# Ethernet.net
KiCad netlist of a schematic drawn in Altium Designer
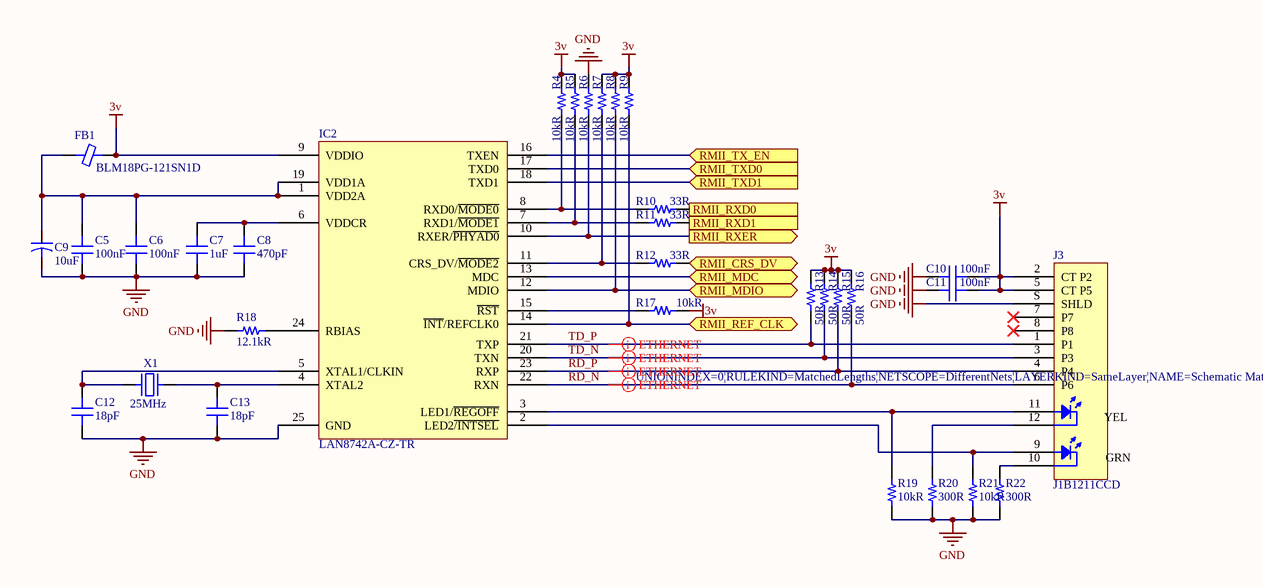
[diagram p0: Ethernet.SchDoc]

(export (version "E")
  (design (tool "Eeschema 10.0.6"))
  (components
    (comp (ref "C5")
      (value "100nF")
      (footprint "CAP 0603/1608")
      (description "Ceramic, SMT Capacitor")
      (fields
        (field (name "MANUFACTURER") "KEMET")
        (field (name "MANUFACTURER PART NUMBER") "C0603C104Z3VACTU")
      )
      (libsource (lib "yildizIoT Library") (part "Capacitor - Ceramic"))
    )
    (comp (ref "C6")
      (value "100nF")
      (footprint "CAP 0603/1608")
      (description "Ceramic, SMT Capacitor")
      (fields
        (field (name "MANUFACTURER") "KEMET")
        (field (name "MANUFACTURER PART NUMBER") "C0603C104Z3VACTU")
      )
      (libsource (lib "yildizIoT Library") (part "Capacitor - Ceramic"))
    )
    (comp (ref "C7")
      (value "1uF")
      (footprint "CAP 0603/1608")
      (description "Ceramic, SMT Capacitor")
      (fields
        (field (name "MANUFACTURER") "Samsung")
        (field (name "MANUFACTURER PART NUMBER") "CL10A105KP8NNNC")
      )
      (libsource (lib "yildizIoT Library") (part "Capacitor - Ceramic"))
    )
    (comp (ref "C8")
      (value "470pF")
      (footprint "CAP 0603/1608")
      (description "Ceramic, SMT Capacitor")
      (fields
        (field (name "MANUFACTURER") "Yageo")
        (field (name "MANUFACTURER PART NUMBER") "CC0603KRX7R9BB471")
      )
      (libsource (lib "yildizIoT Library") (part "Capacitor - Ceramic"))
    )
    (comp (ref "C9")
      (value "10uF")
      (footprint "CAP POL 3216X180N")
      (description "Capacitor, Tantalum")
      (fields
        (field (name "MANUFACTURER") "Vishay Sprague")
        (field (name "MANUFACTURER PART NUMBER") "293D106X0010A2TE3")
      )
      (libsource (lib "yildizIoT Library") (part "Capacitor - Tantalum"))
    )
    (comp (ref "C10")
      (value "100nF")
      (footprint "CAP 0603/1608")
      (description "Ceramic, SMT Capacitor")
      (fields
        (field (name "MANUFACTURER") "KEMET")
        (field (name "MANUFACTURER PART NUMBER") "C0603C104Z3VACTU")
      )
      (libsource (lib "yildizIoT Library") (part "Capacitor - Ceramic"))
    )
    (comp (ref "C11")
      (value "100nF")
      (footprint "CAP 0603/1608")
      (description "Ceramic, SMT Capacitor")
      (fields
        (field (name "MANUFACTURER") "KEMET")
        (field (name "MANUFACTURER PART NUMBER") "C0603C104Z3VACTU")
      )
      (libsource (lib "yildizIoT Library") (part "Capacitor - Ceramic"))
    )
    (comp (ref "C12")
      (value "18pF")
      (footprint "CAP 0603/1608")
      (description "Ceramic, SMT Capacitor")
      (fields
        (field (name "MANUFACTURER") "KEMET")
        (field (name "MANUFACTURER PART NUMBER") "C0603C180J5GACTU")
      )
      (libsource (lib "yildizIoT Library") (part "Capacitor - Ceramic"))
    )
    (comp (ref "C13")
      (value "18pF")
      (footprint "CAP 0603/1608")
      (description "Ceramic, SMT Capacitor")
      (fields
        (field (name "MANUFACTURER") "KEMET")
        (field (name "MANUFACTURER PART NUMBER") "C0603C180J5GACTU")
      )
      (libsource (lib "yildizIoT Library") (part "Capacitor - Ceramic"))
    )
    (comp (ref "FB1")
      (value "BLM18PG-121SN1D")
      (footprint "FER 0603/1608")
      (description "SMT Ferrite Chip")
      (fields (field (name "MANUFACTURER") "Murata") (field (name "TOLERANCE") "25%"))
      (libsource (lib "yildizIoT Library") (part "Ferrite Chip"))
    )
    (comp (ref "IC2")
      (value "LAN8742A-CZ-TR")
      (footprint "SMSC QFN-24 4x4MM")
      (description "Small Footprint RMII 10/100 Ethernet Transceiver with HP\r\nAuto-MDIX and flexPWR® Technology")
      (fields (field (name "MANUFACTURER") "Microchip"))
      (libsource (lib "yildizIoT Library") (part "SMSC LAN8742"))
    )
    (comp (ref "J3")
      (value "J1B1211CCD")
      (footprint "WIZNET J1B1211CCD")
      (fields (field (name "MANUFACTURER") "WIZnet"))
      (libsource (lib "yildizIoT Library") (part "Modular Jack with Magnetics Shield LEDS"))
    )
    (comp (ref "R4")
      (value "10kR")
      (footprint "RES 0603/1608")
      (description "Ceramic, SMT Capacitor")
      (fields
        (field (name "MANUFACTURER") "Stackpole Electronics")
        (field (name "MANUFACTURER PART NUMBER") "RNCP0603FTD10K0")
      )
      (libsource (lib "yildizIoT Library") (part "Resistor_Chip"))
    )
    (comp (ref "R5")
      (value "10kR")
      (footprint "RES 0603/1608")
      (description "Ceramic, SMT Capacitor")
      (fields
        (field (name "MANUFACTURER") "Stackpole Electronics")
        (field (name "MANUFACTURER PART NUMBER") "RNCP0603FTD10K0")
      )
      (libsource (lib "yildizIoT Library") (part "Resistor_Chip"))
    )
    (comp (ref "R6")
      (value "10kR")
      (footprint "RES 0603/1608")
      (description "Ceramic, SMT Capacitor")
      (fields
        (field (name "MANUFACTURER") "Stackpole Electronics")
        (field (name "MANUFACTURER PART NUMBER") "RNCP0603FTD10K0")
      )
      (libsource (lib "yildizIoT Library") (part "Resistor_Chip"))
    )
    (comp (ref "R7")
      (value "10kR")
      (footprint "RES 0603/1608")
      (description "Ceramic, SMT Capacitor")
      (fields
        (field (name "MANUFACTURER") "Stackpole Electronics")
        (field (name "MANUFACTURER PART NUMBER") "RNCP0603FTD10K0")
      )
      (libsource (lib "yildizIoT Library") (part "Resistor_Chip"))
    )
    (comp (ref "R8")
      (value "10kR")
      (footprint "RES 0603/1608")
      (description "Ceramic, SMT Capacitor")
      (fields
        (field (name "MANUFACTURER") "Stackpole Electronics")
        (field (name "MANUFACTURER PART NUMBER") "RNCP0603FTD10K0")
      )
      (libsource (lib "yildizIoT Library") (part "Resistor_Chip"))
    )
    (comp (ref "R9")
      (value "10kR")
      (footprint "RES 0603/1608")
      (description "Ceramic, SMT Capacitor")
      (fields
        (field (name "MANUFACTURER") "Stackpole Electronics")
        (field (name "MANUFACTURER PART NUMBER") "RNCP0603FTD10K0")
      )
      (libsource (lib "yildizIoT Library") (part "Resistor_Chip"))
    )
    (comp (ref "R10")
      (value "33R")
      (footprint "RES 0603/1608")
      (description "Ceramic, SMT Capacitor")
      (fields
        (field (name "MANUFACTURER") "Yageo")
        (field (name "MANUFACTURER PART NUMBER") "RC0603FR-0733RL")
      )
      (libsource (lib "yildizIoT Library") (part "Resistor_Chip"))
    )
    (comp (ref "R11")
      (value "33R")
      (footprint "RES 0603/1608")
      (description "Ceramic, SMT Capacitor")
      (fields
        (field (name "MANUFACTURER") "Yageo")
        (field (name "MANUFACTURER PART NUMBER") "RC0603FR-0733RL")
      )
      (libsource (lib "yildizIoT Library") (part "Resistor_Chip"))
    )
    (comp (ref "R12")
      (value "33R")
      (footprint "RES 0603/1608")
      (description "Ceramic, SMT Capacitor")
      (fields
        (field (name "MANUFACTURER") "Yageo")
        (field (name "MANUFACTURER PART NUMBER") "RC0603FR-0733RL")
      )
      (libsource (lib "yildizIoT Library") (part "Resistor_Chip"))
    )
    (comp (ref "R13")
      (value "50R")
      (footprint "RES 0603/1608")
      (description "Ceramic, SMT Capacitor")
      (fields
        (field (name "MANUFACTURER") "Vishay Dale")
        (field (name "MANUFACTURER PART NUMBER") "CRCW060350R0FKEA")
      )
      (libsource (lib "yildizIoT Library") (part "Resistor_Chip"))
    )
    (comp (ref "R14")
      (value "50R")
      (footprint "RES 0603/1608")
      (description "Ceramic, SMT Capacitor")
      (fields
        (field (name "MANUFACTURER") "Vishay Dale")
        (field (name "MANUFACTURER PART NUMBER") "CRCW060350R0FKEA")
      )
      (libsource (lib "yildizIoT Library") (part "Resistor_Chip"))
    )
    (comp (ref "R15")
      (value "50R")
      (footprint "RES 0603/1608")
      (description "Ceramic, SMT Capacitor")
      (fields
        (field (name "MANUFACTURER") "Vishay Dale")
        (field (name "MANUFACTURER PART NUMBER") "CRCW060350R0FKEA")
      )
      (libsource (lib "yildizIoT Library") (part "Resistor_Chip"))
    )
    (comp (ref "R16")
      (value "50R")
      (footprint "RES 0603/1608")
      (description "Ceramic, SMT Capacitor")
      (fields
        (field (name "MANUFACTURER") "Vishay Dale")
        (field (name "MANUFACTURER PART NUMBER") "CRCW060350R0FKEA")
      )
      (libsource (lib "yildizIoT Library") (part "Resistor_Chip"))
    )
    (comp (ref "R17")
      (value "10kR")
      (footprint "RES 0603/1608")
      (description "Ceramic, SMT Capacitor")
      (fields
        (field (name "MANUFACTURER") "Stackpole Electronics")
        (field (name "MANUFACTURER PART NUMBER") "RNCP0603FTD10K0")
      )
      (libsource (lib "yildizIoT Library") (part "Resistor_Chip"))
    )
    (comp (ref "R18")
      (value "12.1kR")
      (footprint "RES 0603/1608")
      (description "Ceramic, SMT Capacitor")
      (fields
        (field (name "MANUFACTURER") "Stackpole Electronics")
        (field (name "MANUFACTURER PART NUMBER") "RMCF0603FT12K1")
      )
      (libsource (lib "yildizIoT Library") (part "Resistor_Chip"))
    )
    (comp (ref "R19")
      (value "10kR")
      (footprint "RES 0603/1608")
      (description "Ceramic, SMT Capacitor")
      (fields
        (field (name "MANUFACTURER") "Stackpole Electronics")
        (field (name "MANUFACTURER PART NUMBER") "RNCP0603FTD10K0")
      )
      (libsource (lib "yildizIoT Library") (part "Resistor_Chip"))
    )
    (comp (ref "R20")
      (value "300R")
      (footprint "RES 0603/1608")
      (description "Ceramic, SMT Capacitor")
      (fields
        (field (name "MANUFACTURER") "Stackpole Electronics")
        (field (name "MANUFACTURER PART NUMBER") "RMCF0603JT300R")
      )
      (libsource (lib "yildizIoT Library") (part "Resistor_Chip"))
    )
    (comp (ref "R21")
      (value "10kR")
      (footprint "RES 0603/1608")
      (description "Ceramic, SMT Capacitor")
      (fields
        (field (name "MANUFACTURER") "Stackpole Electronics")
        (field (name "MANUFACTURER PART NUMBER") "RNCP0603FTD10K0")
      )
      (libsource (lib "yildizIoT Library") (part "Resistor_Chip"))
    )
    (comp (ref "R22")
      (value "300R")
      (footprint "RES 0603/1608")
      (description "Ceramic, SMT Capacitor")
      (fields
        (field (name "MANUFACTURER") "Stackpole Electronics")
        (field (name "MANUFACTURER PART NUMBER") "RMCF0603JT300R")
      )
      (libsource (lib "yildizIoT Library") (part "Resistor_Chip"))
    )
    (comp (ref "X1")
      (value "25MHz")
      (footprint "ABRACON ABLS")
      (description "SMT Crystal")
      (fields
        (field (name "MANUFACTURER") "Abracon")
        (field (name "MANUFACTURER PART NUMBER") "ABLS-25.000MHZ-16-A-4-H-F-T")
      )
      (libsource (lib "yildizIoT Library") (part "Abracon Crystal ABLS"))
    )
  )
  (nets
    (net (code "1") (name "/RD_N") (class "Default")
      (node (ref "IC2") (pin "22") (pinfunction "RXN_22") (pintype "passive"))
      (node (ref "J3") (pin "6") (pinfunction "P6_6") (pintype "passive"))
      (node (ref "R16") (pin "1") (pinfunction "1_1") (pintype "passive"))
    )
    (net (code "2") (name "/RD_P") (class "Default")
      (node (ref "IC2") (pin "23") (pinfunction "RXP_23") (pintype "passive"))
      (node (ref "J3") (pin "4") (pinfunction "P4_4") (pintype "passive"))
      (node (ref "R15") (pin "1") (pinfunction "1_1") (pintype "passive"))
    )
    (net (code "3") (name "/RMII_CRS_DV") (class "Default")
      (node (ref "R12") (pin "2") (pinfunction "2_2") (pintype "passive"))
    )
    (net (code "4") (name "/RMII_MDC") (class "Default")
      (node (ref "IC2") (pin "13") (pinfunction "MDC_13") (pintype "passive"))
    )
    (net (code "5") (name "/RMII_MDIO") (class "Default")
      (node (ref "IC2") (pin "12") (pinfunction "MDIO_12") (pintype "passive"))
      (node (ref "R8") (pin "2") (pinfunction "2_2") (pintype "passive"))
    )
    (net (code "6") (name "/RMII_REF_CLK") (class "Default")
      (node (ref "IC2") (pin "14") (pinfunction "~{INT}/REFCLK0_14") (pintype "passive"))
      (node (ref "R9") (pin "2") (pinfunction "2_2") (pintype "passive"))
    )
    (net (code "7") (name "/RMII_RXD0") (class "Default")
      (node (ref "R10") (pin "2") (pinfunction "2_2") (pintype "passive"))
    )
    (net (code "8") (name "/RMII_RXD1") (class "Default")
      (node (ref "R11") (pin "2") (pinfunction "2_2") (pintype "passive"))
    )
    (net (code "9") (name "/RMII_RXER") (class "Default")
      (node (ref "IC2") (pin "10") (pinfunction "RXER/~{PHYAD0}_10") (pintype "passive"))
      (node (ref "R6") (pin "2") (pinfunction "2_2") (pintype "passive"))
    )
    (net (code "10") (name "/RMII_TXD0") (class "Default")
      (node (ref "IC2") (pin "17") (pinfunction "TXD0_17") (pintype "passive"))
    )
    (net (code "11") (name "/RMII_TXD1") (class "Default")
      (node (ref "IC2") (pin "18") (pinfunction "TXD1_18") (pintype "passive"))
    )
    (net (code "12") (name "/RMII_TX_EN") (class "Default")
      (node (ref "IC2") (pin "16") (pinfunction "TXEN_16") (pintype "passive"))
    )
    (net (code "13") (name "/TD_N") (class "Default")
      (node (ref "IC2") (pin "20") (pinfunction "TXN_20") (pintype "passive"))
      (node (ref "J3") (pin "3") (pinfunction "P3_3") (pintype "passive"))
      (node (ref "R14") (pin "1") (pinfunction "1_1") (pintype "passive"))
    )
    (net (code "14") (name "/TD_P") (class "Default")
      (node (ref "IC2") (pin "21") (pinfunction "TXP_21") (pintype "passive"))
      (node (ref "J3") (pin "1") (pinfunction "P1_1") (pintype "passive"))
      (node (ref "R13") (pin "1") (pinfunction "1_1") (pintype "passive"))
    )
    (net (code "15") (name "3v") (class "Default")
      (node (ref "C10") (pin "2") (pinfunction "2_2") (pintype "passive"))
      (node (ref "C11") (pin "2") (pinfunction "2_2") (pintype "passive"))
      (node (ref "FB1") (pin "2") (pinfunction "2_2") (pintype "passive"))
      (node (ref "IC2") (pin "9") (pinfunction "VDDIO_9") (pintype "passive"))
      (node (ref "J3") (pin "2") (pinfunction "CT_P2_2") (pintype "passive"))
      (node (ref "J3") (pin "5") (pinfunction "CT_P5_5") (pintype "passive"))
      (node (ref "R13") (pin "2") (pinfunction "2_2") (pintype "passive"))
      (node (ref "R14") (pin "2") (pinfunction "2_2") (pintype "passive"))
      (node (ref "R15") (pin "2") (pinfunction "2_2") (pintype "passive"))
      (node (ref "R16") (pin "2") (pinfunction "2_2") (pintype "passive"))
      (node (ref "R17") (pin "2") (pinfunction "2_2") (pintype "passive"))
      (node (ref "R4") (pin "1") (pinfunction "1_1") (pintype "passive"))
      (node (ref "R5") (pin "1") (pinfunction "1_1") (pintype "passive"))
      (node (ref "R7") (pin "1") (pinfunction "1_1") (pintype "passive"))
      (node (ref "R8") (pin "1") (pinfunction "1_1") (pintype "passive"))
      (node (ref "R9") (pin "1") (pinfunction "1_1") (pintype "passive"))
    )
    (net (code "16") (name "GND") (class "Default")
      (node (ref "C10") (pin "1") (pinfunction "1_1") (pintype "passive"))
      (node (ref "C11") (pin "1") (pinfunction "1_1") (pintype "passive"))
      (node (ref "C12") (pin "1") (pinfunction "1_1") (pintype "passive"))
      (node (ref "C13") (pin "1") (pinfunction "1_1") (pintype "passive"))
      (node (ref "C5") (pin "1") (pinfunction "1_1") (pintype "passive"))
      (node (ref "C6") (pin "1") (pinfunction "1_1") (pintype "passive"))
      (node (ref "C7") (pin "1") (pinfunction "1_1") (pintype "passive"))
      (node (ref "C8") (pin "1") (pinfunction "1_1") (pintype "passive"))
      (node (ref "C9") (pin "1") (pinfunction "1_1") (pintype "passive"))
      (node (ref "IC2") (pin "25") (pinfunction "GND_25") (pintype "passive"))
      (node (ref "J3") (pin "S") (pinfunction "SHLD_S") (pintype "passive"))
      (node (ref "R18") (pin "1") (pinfunction "1_1") (pintype "passive"))
      (node (ref "R19") (pin "2") (pinfunction "2_2") (pintype "passive"))
      (node (ref "R20") (pin "1") (pinfunction "1_1") (pintype "passive"))
      (node (ref "R21") (pin "2") (pinfunction "2_2") (pintype "passive"))
      (node (ref "R22") (pin "1") (pinfunction "1_1") (pintype "passive"))
      (node (ref "R6") (pin "1") (pinfunction "1_1") (pintype "passive"))
    )
    (net (code "17") (name "Net-(IC2-CRS_DV{slash}~{MODE2})") (class "Default")
      (node (ref "IC2") (pin "11") (pinfunction "CRS_DV/~{MODE2}_11") (pintype "passive"))
      (node (ref "R12") (pin "1") (pinfunction "1_1") (pintype "passive"))
      (node (ref "R7") (pin "2") (pinfunction "2_2") (pintype "passive"))
    )
    (net (code "18") (name "Net-(IC2-LED1{slash}~{REGOFF})") (class "Default")
      (node (ref "IC2") (pin "3") (pinfunction "LED1/~{REGOFF}_3") (pintype "passive"))
      (node (ref "J3") (pin "11") (pinfunction "P11_11") (pintype "passive"))
      (node (ref "R19") (pin "1") (pinfunction "1_1") (pintype "passive"))
    )
    (net (code "19") (name "Net-(IC2-LED2~{{slash}INTSEL})") (class "Default")
      (node (ref "IC2") (pin "2") (pinfunction "LED2~{/INTSEL}_2") (pintype "passive"))
      (node (ref "J3") (pin "9") (pinfunction "P9_9") (pintype "passive"))
      (node (ref "R21") (pin "1") (pinfunction "1_1") (pintype "passive"))
    )
    (net (code "20") (name "Net-(IC2-RBIAS)") (class "Default")
      (node (ref "IC2") (pin "24") (pinfunction "RBIAS_24") (pintype "passive"))
      (node (ref "R18") (pin "2") (pinfunction "2_2") (pintype "passive"))
    )
    (net (code "21") (name "Net-(IC2-RXD0{slash}~{MODE0})") (class "Default")
      (node (ref "IC2") (pin "8") (pinfunction "RXD0/~{MODE0}_8") (pintype "passive"))
      (node (ref "R10") (pin "1") (pinfunction "1_1") (pintype "passive"))
      (node (ref "R4") (pin "2") (pinfunction "2_2") (pintype "passive"))
    )
    (net (code "22") (name "Net-(IC2-RXD1{slash}~{MODE1})") (class "Default")
      (node (ref "IC2") (pin "7") (pinfunction "RXD1/~{MODE1}_7") (pintype "passive"))
      (node (ref "R11") (pin "1") (pinfunction "1_1") (pintype "passive"))
      (node (ref "R5") (pin "2") (pinfunction "2_2") (pintype "passive"))
    )
    (net (code "23") (name "Net-(IC2-VDD1A)") (class "Default")
      (node (ref "C5") (pin "2") (pinfunction "2_2") (pintype "passive"))
      (node (ref "C6") (pin "2") (pinfunction "2_2") (pintype "passive"))
      (node (ref "C9") (pin "2") (pinfunction "2_2") (pintype "passive"))
      (node (ref "FB1") (pin "1") (pinfunction "1_1") (pintype "passive"))
      (node (ref "IC2") (pin "1") (pinfunction "VDD2A_1") (pintype "passive"))
      (node (ref "IC2") (pin "19") (pinfunction "VDD1A_19") (pintype "passive"))
    )
    (net (code "24") (name "Net-(IC2-VDDCR)") (class "Default")
      (node (ref "C7") (pin "2") (pinfunction "2_2") (pintype "passive"))
      (node (ref "C8") (pin "2") (pinfunction "2_2") (pintype "passive"))
      (node (ref "IC2") (pin "6") (pinfunction "VDDCR_6") (pintype "passive"))
    )
    (net (code "25") (name "Net-(IC2-XTAL1{slash}CLKIN)") (class "Default")
      (node (ref "C12") (pin "2") (pinfunction "2_2") (pintype "passive"))
      (node (ref "IC2") (pin "5") (pinfunction "XTAL1/CLKIN_5") (pintype "passive"))
      (node (ref "X1") (pin "1") (pinfunction "1_1") (pintype "passive"))
    )
    (net (code "26") (name "Net-(IC2-XTAL2)") (class "Default")
      (node (ref "C13") (pin "2") (pinfunction "2_2") (pintype "passive"))
      (node (ref "IC2") (pin "4") (pinfunction "XTAL2_4") (pintype "passive"))
      (node (ref "X1") (pin "2") (pinfunction "2_2") (pintype "passive"))
    )
    (net (code "27") (name "Net-(IC2-~{RST})") (class "Default")
      (node (ref "IC2") (pin "15") (pinfunction "~{RST}_15") (pintype "passive"))
      (node (ref "R17") (pin "1") (pinfunction "1_1") (pintype "passive"))
    )
    (net (code "28") (name "Net-(J3-P10)") (class "Default")
      (node (ref "J3") (pin "10") (pinfunction "P10_10") (pintype "passive"))
      (node (ref "R22") (pin "2") (pinfunction "2_2") (pintype "passive"))
    )
    (net (code "29") (name "Net-(J3-P12)") (class "Default")
      (node (ref "J3") (pin "12") (pinfunction "P12_12") (pintype "passive"))
      (node (ref "R20") (pin "2") (pinfunction "2_2") (pintype "passive"))
    )
    (net (code "30") (name "unconnected-(J3-P7-Pad7)") (class "Default")
      (node (ref "J3") (pin "7") (pinfunction "P7_7") (pintype "passive+no_connect"))
    )
    (net (code "31") (name "unconnected-(J3-P8-Pad8)") (class "Default")
      (node (ref "J3") (pin "8") (pinfunction "P8_8") (pintype "passive+no_connect"))
    )
  )
)
